# Optotransistor.net
KiCad netlist of a schematic drawn in Altium Designer
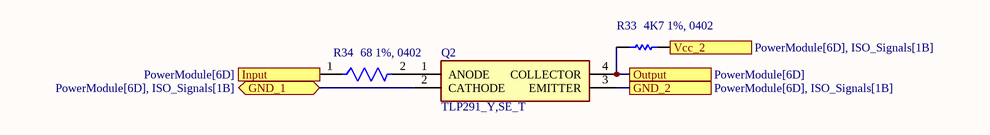
[diagram p0: Optotransistor.SchDoc]

(export (version "E")
  (design (tool "Eeschema 10.0.6"))
  (components
    (comp (ref "Q2")
      (value "TLP291_Y,SE_T")
      (footprint "SamacSys:SOIC127P700X220-4N")
      (description "Phototransistor")
      (fields (field (name "MANUFACTURER_PART_NUMBER") "TLP291(Y,SE(T"))
      (libsource (lib "*") (part "TLP291_Y,SE_T"))
    )
    (comp (ref "R33")
      (value "4K7 1%, 0402")
      (footprint "RESC1005X40X25LL05T05")
      (description "Chip Resistor, 4.7 KOhm, +/- 1%, 0.1 W, -55 to 155 degC, 0402 (1005 Metric), RoHS, Tape and Reel")
      (fields (field (name "TOLERANCE") "1%") (field (name "PARTNUMBER") "ERJ-2RKF4701X"))
      (libsource (lib "Altium Content Vault") (part "RES-2"))
    )
    (comp (ref "R34")
      (value "68 1%, 0402")
      (footprint "FP-ERJ2RK-MFG")
      (fields (field (name "TOLERANCE") "1%"))
      (libsource (lib "Altium Content Vault") (part "1029c3af85768c4190bb7ad29bc67b5"))
    )
  )
  (nets
    (net (code "1") (name "/GND_1") (class "Default")
      (node (ref "Q2") (pin "2") (pinfunction "CATHODE_2") (pintype "passive"))
    )
    (net (code "2") (name "/GND_2") (class "Default")
      (node (ref "Q2") (pin "3") (pinfunction "EMITTER_3") (pintype "passive"))
    )
    (net (code "3") (name "/Input") (class "Default")
      (node (ref "R34") (pin "1") (pinfunction "1_1") (pintype "passive"))
    )
    (net (code "4") (name "/Output") (class "Default")
      (node (ref "Q2") (pin "4") (pinfunction "COLLECTOR_4") (pintype "passive"))
      (node (ref "R33") (pin "2") (pinfunction "2_2") (pintype "passive"))
    )
    (net (code "5") (name "/Vcc_2") (class "Default")
      (node (ref "R33") (pin "1") (pinfunction "1_1") (pintype "passive"))
    )
    (net (code "6") (name "Net-(Q2-ANODE)") (class "Default")
      (node (ref "Q2") (pin "1") (pinfunction "ANODE_1") (pintype "passive"))
      (node (ref "R34") (pin "2") (pinfunction "2_2") (pintype "passive"))
    )
  )
)
